# 2x2_Platine.net
KiCad netlist of a schematic drawn in EAGLE
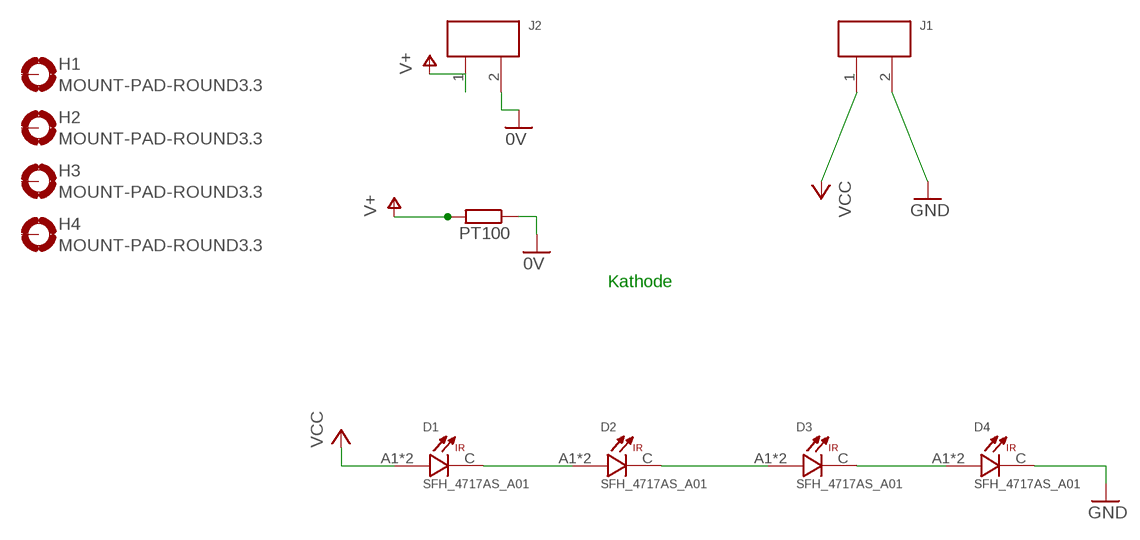
[diagram p0: schematic, sheet 1]

(export (version "E")
  (design (tool "Eeschema 10.0.6"))
  (components
    (comp (ref "D1")
      (value "SFH_4717AS_A01")
      (footprint "eagle-import:LED_SFH_4717AS_A01")
      (fields (field (name "MF") "OSRAM Opto") (field (name "MP") "SFH 4717AS A01"))
      (libsource (lib "eagle-import") (part "SFH_4717AS_A01"))
    )
    (comp (ref "D2")
      (value "SFH_4717AS_A01")
      (footprint "eagle-import:LED_SFH_4717AS_A01")
      (fields (field (name "MF") "OSRAM Opto") (field (name "MP") "SFH 4717AS A01"))
      (libsource (lib "eagle-import") (part "SFH_4717AS_A01"))
    )
    (comp (ref "D3")
      (value "SFH_4717AS_A01")
      (footprint "eagle-import:LED_SFH_4717AS_A01")
      (fields (field (name "MF") "OSRAM Opto") (field (name "MP") "SFH 4717AS A01"))
      (libsource (lib "eagle-import") (part "SFH_4717AS_A01"))
    )
    (comp (ref "D4")
      (value "SFH_4717AS_A01")
      (footprint "eagle-import:LED_SFH_4717AS_A01")
      (fields (field (name "MF") "OSRAM Opto") (field (name "MP") "SFH 4717AS A01"))
      (libsource (lib "eagle-import") (part "SFH_4717AS_A01"))
    )
    (comp (ref "H1")
      (value "MOUNT-PAD-ROUND3.3")
      (footprint "eagle-import:3,3-PAD")
      (libsource (lib "eagle-import") (part "MOUNT-PAD-ROUND3.3"))
    )
    (comp (ref "H2")
      (value "MOUNT-PAD-ROUND3.3")
      (footprint "eagle-import:3,3-PAD")
      (libsource (lib "eagle-import") (part "MOUNT-PAD-ROUND3.3"))
    )
    (comp (ref "H3")
      (value "MOUNT-PAD-ROUND3.3")
      (footprint "eagle-import:3,3-PAD")
      (libsource (lib "eagle-import") (part "MOUNT-PAD-ROUND3.3"))
    )
    (comp (ref "H4")
      (value "MOUNT-PAD-ROUND3.3")
      (footprint "eagle-import:3,3-PAD")
      (libsource (lib "eagle-import") (part "MOUNT-PAD-ROUND3.3"))
    )
    (comp (ref "J1")
      (value "662102145021")
      (footprint "eagle-import:662102145021")
      (libsource (lib "eagle-import") (part "662102145021"))
    )
    (comp (ref "J2")
      (value "662102145021")
      (footprint "eagle-import:662102145021")
      (libsource (lib "eagle-import") (part "662102145021"))
    )
    (comp (ref "PT100")
      (value "R-EU_R0603")
      (footprint "eagle-import:R0603")
      (libsource (lib "eagle-import") (part "R-EU_R0603"))
    )
  )
  (nets
    (net (code "1") (name "0V") (class "Default")
      (node (ref "J2") (pin "2") (pinfunction "1_2") (pintype "passive"))
      (node (ref "PT100") (pin "1") (pinfunction "1_1") (pintype "passive"))
    )
    (net (code "2") (name "GND") (class "Default")
      (node (ref "D4") (pin "C") (pinfunction "C_C") (pintype "passive"))
      (node (ref "J1") (pin "2") (pinfunction "1_2") (pintype "passive"))
    )
    (net (code "3") (name "Net-(D1-PadC)") (class "Default")
      (node (ref "D1") (pin "C") (pinfunction "C_C") (pintype "passive"))
      (node (ref "D2") (pin "A1") (pinfunction "A_A1") (pintype "passive"))
      (node (ref "D2") (pin "A2") (pinfunction "A_A2") (pintype "passive"))
    )
    (net (code "4") (name "Net-(D2-PadC)") (class "Default")
      (node (ref "D2") (pin "C") (pinfunction "C_C") (pintype "passive"))
      (node (ref "D3") (pin "A1") (pinfunction "A_A1") (pintype "passive"))
      (node (ref "D3") (pin "A2") (pinfunction "A_A2") (pintype "passive"))
    )
    (net (code "5") (name "Net-(D3-PadC)") (class "Default")
      (node (ref "D3") (pin "C") (pinfunction "C_C") (pintype "passive"))
      (node (ref "D4") (pin "A1") (pinfunction "A_A1") (pintype "passive"))
      (node (ref "D4") (pin "A2") (pinfunction "A_A2") (pintype "passive"))
    )
    (net (code "6") (name "V+") (class "Default")
      (node (ref "J2") (pin "1") (pinfunction "2_1") (pintype "passive"))
      (node (ref "PT100") (pin "2") (pinfunction "2_2") (pintype "passive"))
    )
    (net (code "7") (name "VCC") (class "Default")
      (node (ref "D1") (pin "A1") (pinfunction "A_A1") (pintype "passive"))
      (node (ref "D1") (pin "A2") (pinfunction "A_A2") (pintype "passive"))
      (node (ref "J1") (pin "1") (pinfunction "2_1") (pintype "passive"))
    )
    (net (code "8") (name "unconnected-(H1-MOUNT-PadB3,3)") (class "Default")
      (node (ref "H1") (pin "B3,3") (pinfunction "MOUNT_B3,3") (pintype "passive"))
    )
    (net (code "9") (name "unconnected-(H2-MOUNT-PadB3,3)") (class "Default")
      (node (ref "H2") (pin "B3,3") (pinfunction "MOUNT_B3,3") (pintype "passive"))
    )
    (net (code "10") (name "unconnected-(H3-MOUNT-PadB3,3)") (class "Default")
      (node (ref "H3") (pin "B3,3") (pinfunction "MOUNT_B3,3") (pintype "passive"))
    )
    (net (code "11") (name "unconnected-(H4-MOUNT-PadB3,3)") (class "Default")
      (node (ref "H4") (pin "B3,3") (pinfunction "MOUNT_B3,3") (pintype "passive"))
    )
  )
)
